# Light.net
KiCad netlist of a schematic drawn in Altium Designer
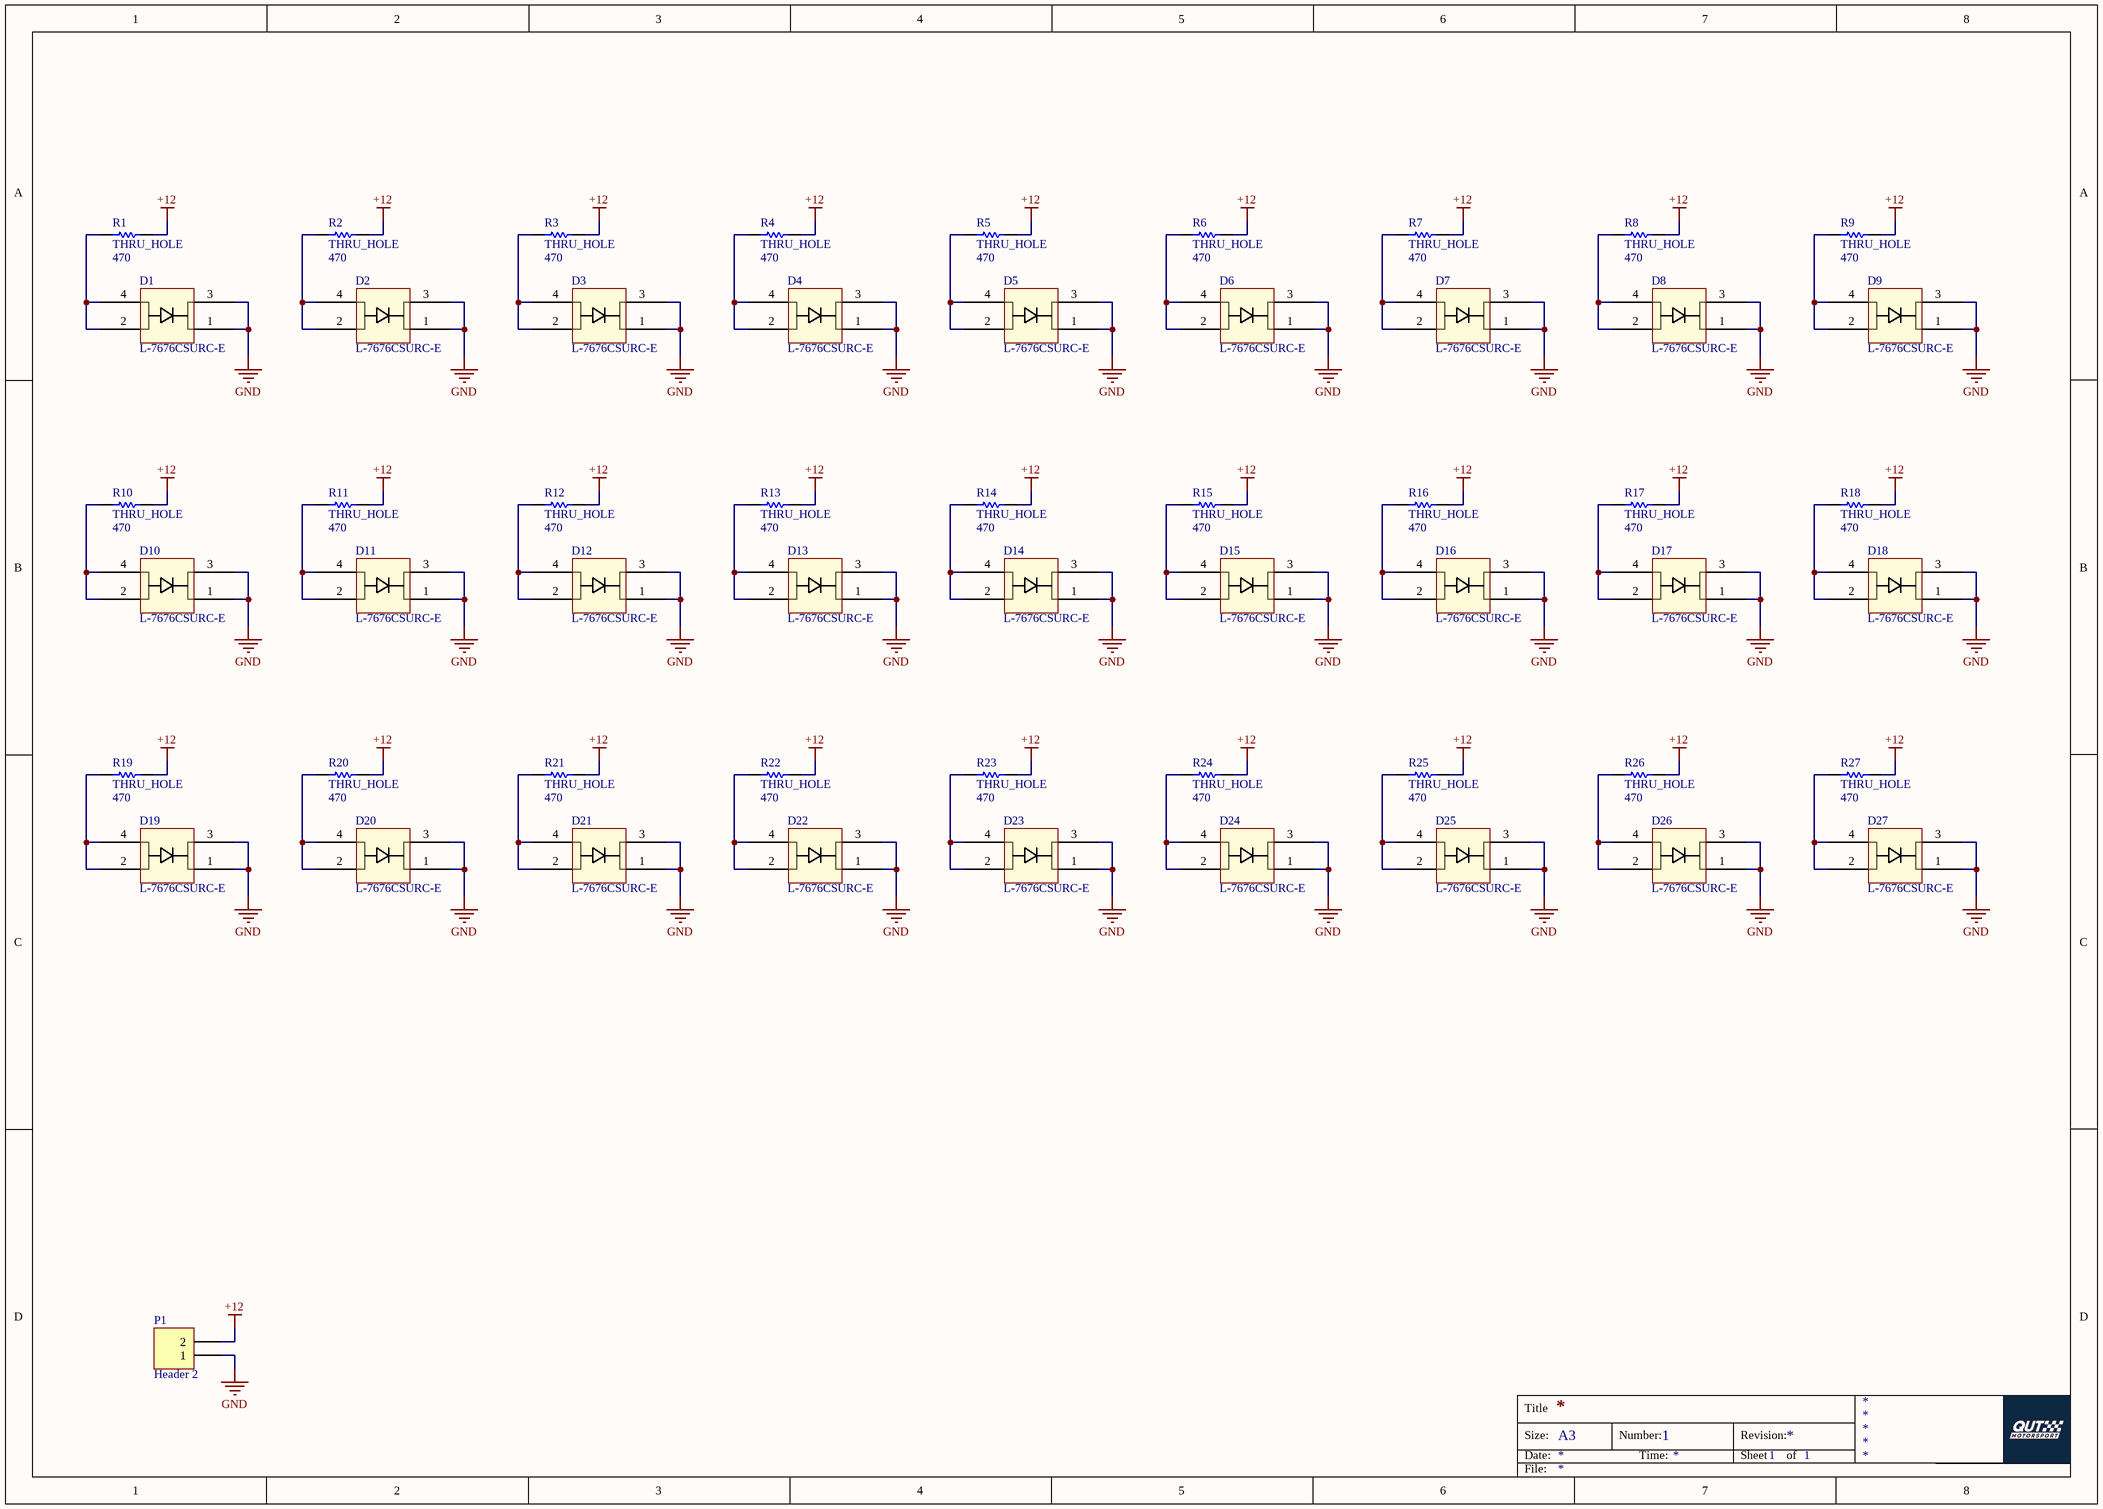
[diagram p0: Light.SchDoc]

(export (version "E")
  (design (tool "Eeschema 10.0.6"))
  (components
    (comp (ref "D1")
      (value "L-7676CSURC-E")
      (footprint "L-7676CSURC-E")
      (libsource (lib "BrightLED") (part "L-7676CSURC-E"))
    )
    (comp (ref "D2")
      (value "L-7676CSURC-E")
      (footprint "L-7676CSURC-E")
      (libsource (lib "BrightLED") (part "L-7676CSURC-E"))
    )
    (comp (ref "D3")
      (value "L-7676CSURC-E")
      (footprint "L-7676CSURC-E")
      (libsource (lib "BrightLED") (part "L-7676CSURC-E"))
    )
    (comp (ref "D4")
      (value "L-7676CSURC-E")
      (footprint "L-7676CSURC-E")
      (libsource (lib "BrightLED") (part "L-7676CSURC-E"))
    )
    (comp (ref "D5")
      (value "L-7676CSURC-E")
      (footprint "L-7676CSURC-E")
      (libsource (lib "BrightLED") (part "L-7676CSURC-E"))
    )
    (comp (ref "D6")
      (value "L-7676CSURC-E")
      (footprint "L-7676CSURC-E")
      (libsource (lib "BrightLED") (part "L-7676CSURC-E"))
    )
    (comp (ref "D7")
      (value "L-7676CSURC-E")
      (footprint "L-7676CSURC-E")
      (libsource (lib "BrightLED") (part "L-7676CSURC-E"))
    )
    (comp (ref "D8")
      (value "L-7676CSURC-E")
      (footprint "L-7676CSURC-E")
      (libsource (lib "BrightLED") (part "L-7676CSURC-E"))
    )
    (comp (ref "D9")
      (value "L-7676CSURC-E")
      (footprint "L-7676CSURC-E")
      (libsource (lib "BrightLED") (part "L-7676CSURC-E"))
    )
    (comp (ref "D10")
      (value "L-7676CSURC-E")
      (footprint "L-7676CSURC-E")
      (libsource (lib "BrightLED") (part "L-7676CSURC-E"))
    )
    (comp (ref "D11")
      (value "L-7676CSURC-E")
      (footprint "L-7676CSURC-E")
      (libsource (lib "BrightLED") (part "L-7676CSURC-E"))
    )
    (comp (ref "D12")
      (value "L-7676CSURC-E")
      (footprint "L-7676CSURC-E")
      (libsource (lib "BrightLED") (part "L-7676CSURC-E"))
    )
    (comp (ref "D13")
      (value "L-7676CSURC-E")
      (footprint "L-7676CSURC-E")
      (libsource (lib "BrightLED") (part "L-7676CSURC-E"))
    )
    (comp (ref "D14")
      (value "L-7676CSURC-E")
      (footprint "L-7676CSURC-E")
      (libsource (lib "BrightLED") (part "L-7676CSURC-E"))
    )
    (comp (ref "D15")
      (value "L-7676CSURC-E")
      (footprint "L-7676CSURC-E")
      (libsource (lib "BrightLED") (part "L-7676CSURC-E"))
    )
    (comp (ref "D16")
      (value "L-7676CSURC-E")
      (footprint "L-7676CSURC-E")
      (libsource (lib "BrightLED") (part "L-7676CSURC-E"))
    )
    (comp (ref "D17")
      (value "L-7676CSURC-E")
      (footprint "L-7676CSURC-E")
      (libsource (lib "BrightLED") (part "L-7676CSURC-E"))
    )
    (comp (ref "D18")
      (value "L-7676CSURC-E")
      (footprint "L-7676CSURC-E")
      (libsource (lib "BrightLED") (part "L-7676CSURC-E"))
    )
    (comp (ref "D19")
      (value "L-7676CSURC-E")
      (footprint "L-7676CSURC-E")
      (libsource (lib "BrightLED") (part "L-7676CSURC-E"))
    )
    (comp (ref "D20")
      (value "L-7676CSURC-E")
      (footprint "L-7676CSURC-E")
      (libsource (lib "BrightLED") (part "L-7676CSURC-E"))
    )
    (comp (ref "D21")
      (value "L-7676CSURC-E")
      (footprint "L-7676CSURC-E")
      (libsource (lib "BrightLED") (part "L-7676CSURC-E"))
    )
    (comp (ref "D22")
      (value "L-7676CSURC-E")
      (footprint "L-7676CSURC-E")
      (libsource (lib "BrightLED") (part "L-7676CSURC-E"))
    )
    (comp (ref "D23")
      (value "L-7676CSURC-E")
      (footprint "L-7676CSURC-E")
      (libsource (lib "BrightLED") (part "L-7676CSURC-E"))
    )
    (comp (ref "D24")
      (value "L-7676CSURC-E")
      (footprint "L-7676CSURC-E")
      (libsource (lib "BrightLED") (part "L-7676CSURC-E"))
    )
    (comp (ref "D25")
      (value "L-7676CSURC-E")
      (footprint "L-7676CSURC-E")
      (libsource (lib "BrightLED") (part "L-7676CSURC-E"))
    )
    (comp (ref "D26")
      (value "L-7676CSURC-E")
      (footprint "L-7676CSURC-E")
      (libsource (lib "BrightLED") (part "L-7676CSURC-E"))
    )
    (comp (ref "D27")
      (value "L-7676CSURC-E")
      (footprint "L-7676CSURC-E")
      (libsource (lib "BrightLED") (part "L-7676CSURC-E"))
    )
    (comp (ref "P1")
      (value "Header 2")
      (footprint "HDR1X2")
      (description "Header, 2-Pin")
      (fields (field (name "PUBLISHER") "Altium Limited"))
      (libsource (lib "Miscellaneous Connectors") (part "Header 2"))
    )
    (comp (ref "R1")
      (value "THRU_HOLE")
      (footprint "AXIAL-0.3")
      (description "Resistor")
      (fields (field (name "ALTIUM_VALUE") "470") (field (name "PUBLISHER") "Altium Limited"))
      (libsource (lib "Miscellaneous Devices") (part "Res1"))
    )
    (comp (ref "R2")
      (value "THRU_HOLE")
      (footprint "AXIAL-0.3")
      (description "Resistor")
      (fields (field (name "ALTIUM_VALUE") "470") (field (name "PUBLISHER") "Altium Limited"))
      (libsource (lib "Miscellaneous Devices") (part "Res1"))
    )
    (comp (ref "R3")
      (value "THRU_HOLE")
      (footprint "AXIAL-0.3")
      (description "Resistor")
      (fields (field (name "ALTIUM_VALUE") "470") (field (name "PUBLISHER") "Altium Limited"))
      (libsource (lib "Miscellaneous Devices") (part "Res1"))
    )
    (comp (ref "R4")
      (value "THRU_HOLE")
      (footprint "AXIAL-0.3")
      (description "Resistor")
      (fields (field (name "ALTIUM_VALUE") "470") (field (name "PUBLISHER") "Altium Limited"))
      (libsource (lib "Miscellaneous Devices") (part "Res1"))
    )
    (comp (ref "R5")
      (value "THRU_HOLE")
      (footprint "AXIAL-0.3")
      (description "Resistor")
      (fields (field (name "ALTIUM_VALUE") "470") (field (name "PUBLISHER") "Altium Limited"))
      (libsource (lib "Miscellaneous Devices") (part "Res1"))
    )
    (comp (ref "R6")
      (value "THRU_HOLE")
      (footprint "AXIAL-0.3")
      (description "Resistor")
      (fields (field (name "ALTIUM_VALUE") "470") (field (name "PUBLISHER") "Altium Limited"))
      (libsource (lib "Miscellaneous Devices") (part "Res1"))
    )
    (comp (ref "R7")
      (value "THRU_HOLE")
      (footprint "AXIAL-0.3")
      (description "Resistor")
      (fields (field (name "ALTIUM_VALUE") "470") (field (name "PUBLISHER") "Altium Limited"))
      (libsource (lib "Miscellaneous Devices") (part "Res1"))
    )
    (comp (ref "R8")
      (value "THRU_HOLE")
      (footprint "AXIAL-0.3")
      (description "Resistor")
      (fields (field (name "ALTIUM_VALUE") "470") (field (name "PUBLISHER") "Altium Limited"))
      (libsource (lib "Miscellaneous Devices") (part "Res1"))
    )
    (comp (ref "R9")
      (value "THRU_HOLE")
      (footprint "AXIAL-0.3")
      (description "Resistor")
      (fields (field (name "ALTIUM_VALUE") "470") (field (name "PUBLISHER") "Altium Limited"))
      (libsource (lib "Miscellaneous Devices") (part "Res1"))
    )
    (comp (ref "R10")
      (value "THRU_HOLE")
      (footprint "AXIAL-0.3")
      (description "Resistor")
      (fields (field (name "ALTIUM_VALUE") "470") (field (name "PUBLISHER") "Altium Limited"))
      (libsource (lib "Miscellaneous Devices") (part "Res1"))
    )
    (comp (ref "R11")
      (value "THRU_HOLE")
      (footprint "AXIAL-0.3")
      (description "Resistor")
      (fields (field (name "ALTIUM_VALUE") "470") (field (name "PUBLISHER") "Altium Limited"))
      (libsource (lib "Miscellaneous Devices") (part "Res1"))
    )
    (comp (ref "R12")
      (value "THRU_HOLE")
      (footprint "AXIAL-0.3")
      (description "Resistor")
      (fields (field (name "ALTIUM_VALUE") "470") (field (name "PUBLISHER") "Altium Limited"))
      (libsource (lib "Miscellaneous Devices") (part "Res1"))
    )
    (comp (ref "R13")
      (value "THRU_HOLE")
      (footprint "AXIAL-0.3")
      (description "Resistor")
      (fields (field (name "ALTIUM_VALUE") "470") (field (name "PUBLISHER") "Altium Limited"))
      (libsource (lib "Miscellaneous Devices") (part "Res1"))
    )
    (comp (ref "R14")
      (value "THRU_HOLE")
      (footprint "AXIAL-0.3")
      (description "Resistor")
      (fields (field (name "ALTIUM_VALUE") "470") (field (name "PUBLISHER") "Altium Limited"))
      (libsource (lib "Miscellaneous Devices") (part "Res1"))
    )
    (comp (ref "R15")
      (value "THRU_HOLE")
      (footprint "AXIAL-0.3")
      (description "Resistor")
      (fields (field (name "ALTIUM_VALUE") "470") (field (name "PUBLISHER") "Altium Limited"))
      (libsource (lib "Miscellaneous Devices") (part "Res1"))
    )
    (comp (ref "R16")
      (value "THRU_HOLE")
      (footprint "AXIAL-0.3")
      (description "Resistor")
      (fields (field (name "ALTIUM_VALUE") "470") (field (name "PUBLISHER") "Altium Limited"))
      (libsource (lib "Miscellaneous Devices") (part "Res1"))
    )
    (comp (ref "R17")
      (value "THRU_HOLE")
      (footprint "AXIAL-0.3")
      (description "Resistor")
      (fields (field (name "ALTIUM_VALUE") "470") (field (name "PUBLISHER") "Altium Limited"))
      (libsource (lib "Miscellaneous Devices") (part "Res1"))
    )
    (comp (ref "R18")
      (value "THRU_HOLE")
      (footprint "AXIAL-0.3")
      (description "Resistor")
      (fields (field (name "ALTIUM_VALUE") "470") (field (name "PUBLISHER") "Altium Limited"))
      (libsource (lib "Miscellaneous Devices") (part "Res1"))
    )
    (comp (ref "R19")
      (value "THRU_HOLE")
      (footprint "AXIAL-0.3")
      (description "Resistor")
      (fields (field (name "ALTIUM_VALUE") "470") (field (name "PUBLISHER") "Altium Limited"))
      (libsource (lib "Miscellaneous Devices") (part "Res1"))
    )
    (comp (ref "R20")
      (value "THRU_HOLE")
      (footprint "AXIAL-0.3")
      (description "Resistor")
      (fields (field (name "ALTIUM_VALUE") "470") (field (name "PUBLISHER") "Altium Limited"))
      (libsource (lib "Miscellaneous Devices") (part "Res1"))
    )
    (comp (ref "R21")
      (value "THRU_HOLE")
      (footprint "AXIAL-0.3")
      (description "Resistor")
      (fields (field (name "ALTIUM_VALUE") "470") (field (name "PUBLISHER") "Altium Limited"))
      (libsource (lib "Miscellaneous Devices") (part "Res1"))
    )
    (comp (ref "R22")
      (value "THRU_HOLE")
      (footprint "AXIAL-0.3")
      (description "Resistor")
      (fields (field (name "ALTIUM_VALUE") "470") (field (name "PUBLISHER") "Altium Limited"))
      (libsource (lib "Miscellaneous Devices") (part "Res1"))
    )
    (comp (ref "R23")
      (value "THRU_HOLE")
      (footprint "AXIAL-0.3")
      (description "Resistor")
      (fields (field (name "ALTIUM_VALUE") "470") (field (name "PUBLISHER") "Altium Limited"))
      (libsource (lib "Miscellaneous Devices") (part "Res1"))
    )
    (comp (ref "R24")
      (value "THRU_HOLE")
      (footprint "AXIAL-0.3")
      (description "Resistor")
      (fields (field (name "ALTIUM_VALUE") "470") (field (name "PUBLISHER") "Altium Limited"))
      (libsource (lib "Miscellaneous Devices") (part "Res1"))
    )
    (comp (ref "R25")
      (value "THRU_HOLE")
      (footprint "AXIAL-0.3")
      (description "Resistor")
      (fields (field (name "ALTIUM_VALUE") "470") (field (name "PUBLISHER") "Altium Limited"))
      (libsource (lib "Miscellaneous Devices") (part "Res1"))
    )
    (comp (ref "R26")
      (value "THRU_HOLE")
      (footprint "AXIAL-0.3")
      (description "Resistor")
      (fields (field (name "ALTIUM_VALUE") "470") (field (name "PUBLISHER") "Altium Limited"))
      (libsource (lib "Miscellaneous Devices") (part "Res1"))
    )
    (comp (ref "R27")
      (value "THRU_HOLE")
      (footprint "AXIAL-0.3")
      (description "Resistor")
      (fields (field (name "ALTIUM_VALUE") "470") (field (name "PUBLISHER") "Altium Limited"))
      (libsource (lib "Miscellaneous Devices") (part "Res1"))
    )
  )
  (nets
    (net (code "1") (name "+12") (class "Default")
      (node (ref "P1") (pin "2") (pinfunction "2_2") (pintype "passive"))
      (node (ref "R1") (pin "2") (pinfunction "2_2") (pintype "passive"))
      (node (ref "R10") (pin "2") (pinfunction "2_2") (pintype "passive"))
      (node (ref "R11") (pin "2") (pinfunction "2_2") (pintype "passive"))
      (node (ref "R12") (pin "2") (pinfunction "2_2") (pintype "passive"))
      (node (ref "R13") (pin "2") (pinfunction "2_2") (pintype "passive"))
      (node (ref "R14") (pin "2") (pinfunction "2_2") (pintype "passive"))
      (node (ref "R15") (pin "2") (pinfunction "2_2") (pintype "passive"))
      (node (ref "R16") (pin "2") (pinfunction "2_2") (pintype "passive"))
      (node (ref "R17") (pin "2") (pinfunction "2_2") (pintype "passive"))
      (node (ref "R18") (pin "2") (pinfunction "2_2") (pintype "passive"))
      (node (ref "R19") (pin "2") (pinfunction "2_2") (pintype "passive"))
      (node (ref "R2") (pin "2") (pinfunction "2_2") (pintype "passive"))
      (node (ref "R20") (pin "2") (pinfunction "2_2") (pintype "passive"))
      (node (ref "R21") (pin "2") (pinfunction "2_2") (pintype "passive"))
      (node (ref "R22") (pin "2") (pinfunction "2_2") (pintype "passive"))
      (node (ref "R23") (pin "2") (pinfunction "2_2") (pintype "passive"))
      (node (ref "R24") (pin "2") (pinfunction "2_2") (pintype "passive"))
      (node (ref "R25") (pin "2") (pinfunction "2_2") (pintype "passive"))
      (node (ref "R26") (pin "2") (pinfunction "2_2") (pintype "passive"))
      (node (ref "R27") (pin "2") (pinfunction "2_2") (pintype "passive"))
      (node (ref "R3") (pin "2") (pinfunction "2_2") (pintype "passive"))
      (node (ref "R4") (pin "2") (pinfunction "2_2") (pintype "passive"))
      (node (ref "R5") (pin "2") (pinfunction "2_2") (pintype "passive"))
      (node (ref "R6") (pin "2") (pinfunction "2_2") (pintype "passive"))
      (node (ref "R7") (pin "2") (pinfunction "2_2") (pintype "passive"))
      (node (ref "R8") (pin "2") (pinfunction "2_2") (pintype "passive"))
      (node (ref "R9") (pin "2") (pinfunction "2_2") (pintype "passive"))
    )
    (net (code "2") (name "GND") (class "Default")
      (node (ref "D1") (pin "1") (pinfunction "0_1") (pintype "passive"))
      (node (ref "D1") (pin "3") (pinfunction "0_3") (pintype "passive"))
      (node (ref "D10") (pin "1") (pinfunction "0_1") (pintype "passive"))
      (node (ref "D10") (pin "3") (pinfunction "0_3") (pintype "passive"))
      (node (ref "D11") (pin "1") (pinfunction "0_1") (pintype "passive"))
      (node (ref "D11") (pin "3") (pinfunction "0_3") (pintype "passive"))
      (node (ref "D12") (pin "1") (pinfunction "0_1") (pintype "passive"))
      (node (ref "D12") (pin "3") (pinfunction "0_3") (pintype "passive"))
      (node (ref "D13") (pin "1") (pinfunction "0_1") (pintype "passive"))
      (node (ref "D13") (pin "3") (pinfunction "0_3") (pintype "passive"))
      (node (ref "D14") (pin "1") (pinfunction "0_1") (pintype "passive"))
      (node (ref "D14") (pin "3") (pinfunction "0_3") (pintype "passive"))
      (node (ref "D15") (pin "1") (pinfunction "0_1") (pintype "passive"))
      (node (ref "D15") (pin "3") (pinfunction "0_3") (pintype "passive"))
      (node (ref "D16") (pin "1") (pinfunction "0_1") (pintype "passive"))
      (node (ref "D16") (pin "3") (pinfunction "0_3") (pintype "passive"))
      (node (ref "D17") (pin "1") (pinfunction "0_1") (pintype "passive"))
      (node (ref "D17") (pin "3") (pinfunction "0_3") (pintype "passive"))
      (node (ref "D18") (pin "1") (pinfunction "0_1") (pintype "passive"))
      (node (ref "D18") (pin "3") (pinfunction "0_3") (pintype "passive"))
      (node (ref "D19") (pin "1") (pinfunction "0_1") (pintype "passive"))
      (node (ref "D19") (pin "3") (pinfunction "0_3") (pintype "passive"))
      (node (ref "D2") (pin "1") (pinfunction "0_1") (pintype "passive"))
      (node (ref "D2") (pin "3") (pinfunction "0_3") (pintype "passive"))
      (node (ref "D20") (pin "1") (pinfunction "0_1") (pintype "passive"))
      (node (ref "D20") (pin "3") (pinfunction "0_3") (pintype "passive"))
      (node (ref "D21") (pin "1") (pinfunction "0_1") (pintype "passive"))
      (node (ref "D21") (pin "3") (pinfunction "0_3") (pintype "passive"))
      (node (ref "D22") (pin "1") (pinfunction "0_1") (pintype "passive"))
      (node (ref "D22") (pin "3") (pinfunction "0_3") (pintype "passive"))
      (node (ref "D23") (pin "1") (pinfunction "0_1") (pintype "passive"))
      (node (ref "D23") (pin "3") (pinfunction "0_3") (pintype "passive"))
      (node (ref "D24") (pin "1") (pinfunction "0_1") (pintype "passive"))
      (node (ref "D24") (pin "3") (pinfunction "0_3") (pintype "passive"))
      (node (ref "D25") (pin "1") (pinfunction "0_1") (pintype "passive"))
      (node (ref "D25") (pin "3") (pinfunction "0_3") (pintype "passive"))
      (node (ref "D26") (pin "1") (pinfunction "0_1") (pintype "passive"))
      (node (ref "D26") (pin "3") (pinfunction "0_3") (pintype "passive"))
      (node (ref "D27") (pin "1") (pinfunction "0_1") (pintype "passive"))
      (node (ref "D27") (pin "3") (pinfunction "0_3") (pintype "passive"))
      (node (ref "D3") (pin "1") (pinfunction "0_1") (pintype "passive"))
      (node (ref "D3") (pin "3") (pinfunction "0_3") (pintype "passive"))
      (node (ref "D4") (pin "1") (pinfunction "0_1") (pintype "passive"))
      (node (ref "D4") (pin "3") (pinfunction "0_3") (pintype "passive"))
      (node (ref "D5") (pin "1") (pinfunction "0_1") (pintype "passive"))
      (node (ref "D5") (pin "3") (pinfunction "0_3") (pintype "passive"))
      (node (ref "D6") (pin "1") (pinfunction "0_1") (pintype "passive"))
      (node (ref "D6") (pin "3") (pinfunction "0_3") (pintype "passive"))
      (node (ref "D7") (pin "1") (pinfunction "0_1") (pintype "passive"))
      (node (ref "D7") (pin "3") (pinfunction "0_3") (pintype "passive"))
      (node (ref "D8") (pin "1") (pinfunction "0_1") (pintype "passive"))
      (node (ref "D8") (pin "3") (pinfunction "0_3") (pintype "passive"))
      (node (ref "D9") (pin "1") (pinfunction "0_1") (pintype "passive"))
      (node (ref "D9") (pin "3") (pinfunction "0_3") (pintype "passive"))
      (node (ref "P1") (pin "1") (pinfunction "1_1") (pintype "passive"))
    )
    (net (code "3") (name "Net-(D1-0-Pad2)") (class "Default")
      (node (ref "D1") (pin "2") (pinfunction "0_2") (pintype "passive"))
      (node (ref "D1") (pin "4") (pinfunction "0_4") (pintype "passive"))
      (node (ref "R1") (pin "1") (pinfunction "1_1") (pintype "passive"))
    )
    (net (code "4") (name "Net-(D2-0-Pad2)") (class "Default")
      (node (ref "D2") (pin "2") (pinfunction "0_2") (pintype "passive"))
      (node (ref "D2") (pin "4") (pinfunction "0_4") (pintype "passive"))
      (node (ref "R2") (pin "1") (pinfunction "1_1") (pintype "passive"))
    )
    (net (code "5") (name "Net-(D3-0-Pad2)") (class "Default")
      (node (ref "D3") (pin "2") (pinfunction "0_2") (pintype "passive"))
      (node (ref "D3") (pin "4") (pinfunction "0_4") (pintype "passive"))
      (node (ref "R3") (pin "1") (pinfunction "1_1") (pintype "passive"))
    )
    (net (code "6") (name "Net-(D4-0-Pad2)") (class "Default")
      (node (ref "D4") (pin "2") (pinfunction "0_2") (pintype "passive"))
      (node (ref "D4") (pin "4") (pinfunction "0_4") (pintype "passive"))
      (node (ref "R4") (pin "1") (pinfunction "1_1") (pintype "passive"))
    )
    (net (code "7") (name "Net-(D5-0-Pad2)") (class "Default")
      (node (ref "D5") (pin "2") (pinfunction "0_2") (pintype "passive"))
      (node (ref "D5") (pin "4") (pinfunction "0_4") (pintype "passive"))
      (node (ref "R5") (pin "1") (pinfunction "1_1") (pintype "passive"))
    )
    (net (code "8") (name "Net-(D6-0-Pad2)") (class "Default")
      (node (ref "D6") (pin "2") (pinfunction "0_2") (pintype "passive"))
      (node (ref "D6") (pin "4") (pinfunction "0_4") (pintype "passive"))
      (node (ref "R6") (pin "1") (pinfunction "1_1") (pintype "passive"))
    )
    (net (code "9") (name "Net-(D7-0-Pad2)") (class "Default")
      (node (ref "D7") (pin "2") (pinfunction "0_2") (pintype "passive"))
      (node (ref "D7") (pin "4") (pinfunction "0_4") (pintype "passive"))
      (node (ref "R7") (pin "1") (pinfunction "1_1") (pintype "passive"))
    )
    (net (code "10") (name "Net-(D8-0-Pad2)") (class "Default")
      (node (ref "D8") (pin "2") (pinfunction "0_2") (pintype "passive"))
      (node (ref "D8") (pin "4") (pinfunction "0_4") (pintype "passive"))
      (node (ref "R8") (pin "1") (pinfunction "1_1") (pintype "passive"))
    )
    (net (code "11") (name "Net-(D9-0-Pad2)") (class "Default")
      (node (ref "D9") (pin "2") (pinfunction "0_2") (pintype "passive"))
      (node (ref "D9") (pin "4") (pinfunction "0_4") (pintype "passive"))
      (node (ref "R9") (pin "1") (pinfunction "1_1") (pintype "passive"))
    )
    (net (code "12") (name "Net-(D10-0-Pad2)") (class "Default")
      (node (ref "D10") (pin "2") (pinfunction "0_2") (pintype "passive"))
      (node (ref "D10") (pin "4") (pinfunction "0_4") (pintype "passive"))
      (node (ref "R10") (pin "1") (pinfunction "1_1") (pintype "passive"))
    )
    (net (code "13") (name "Net-(D11-0-Pad2)") (class "Default")
      (node (ref "D11") (pin "2") (pinfunction "0_2") (pintype "passive"))
      (node (ref "D11") (pin "4") (pinfunction "0_4") (pintype "passive"))
      (node (ref "R11") (pin "1") (pinfunction "1_1") (pintype "passive"))
    )
    (net (code "14") (name "Net-(D12-0-Pad2)") (class "Default")
      (node (ref "D12") (pin "2") (pinfunction "0_2") (pintype "passive"))
      (node (ref "D12") (pin "4") (pinfunction "0_4") (pintype "passive"))
      (node (ref "R12") (pin "1") (pinfunction "1_1") (pintype "passive"))
    )
    (net (code "15") (name "Net-(D13-0-Pad2)") (class "Default")
      (node (ref "D13") (pin "2") (pinfunction "0_2") (pintype "passive"))
      (node (ref "D13") (pin "4") (pinfunction "0_4") (pintype "passive"))
      (node (ref "R13") (pin "1") (pinfunction "1_1") (pintype "passive"))
    )
    (net (code "16") (name "Net-(D14-0-Pad2)") (class "Default")
      (node (ref "D14") (pin "2") (pinfunction "0_2") (pintype "passive"))
      (node (ref "D14") (pin "4") (pinfunction "0_4") (pintype "passive"))
      (node (ref "R14") (pin "1") (pinfunction "1_1") (pintype "passive"))
    )
    (net (code "17") (name "Net-(D15-0-Pad2)") (class "Default")
      (node (ref "D15") (pin "2") (pinfunction "0_2") (pintype "passive"))
      (node (ref "D15") (pin "4") (pinfunction "0_4") (pintype "passive"))
      (node (ref "R15") (pin "1") (pinfunction "1_1") (pintype "passive"))
    )
    (net (code "18") (name "Net-(D16-0-Pad2)") (class "Default")
      (node (ref "D16") (pin "2") (pinfunction "0_2") (pintype "passive"))
      (node (ref "D16") (pin "4") (pinfunction "0_4") (pintype "passive"))
      (node (ref "R16") (pin "1") (pinfunction "1_1") (pintype "passive"))
    )
    (net (code "19") (name "Net-(D17-0-Pad2)") (class "Default")
      (node (ref "D17") (pin "2") (pinfunction "0_2") (pintype "passive"))
      (node (ref "D17") (pin "4") (pinfunction "0_4") (pintype "passive"))
      (node (ref "R17") (pin "1") (pinfunction "1_1") (pintype "passive"))
    )
    (net (code "20") (name "Net-(D18-0-Pad2)") (class "Default")
      (node (ref "D18") (pin "2") (pinfunction "0_2") (pintype "passive"))
      (node (ref "D18") (pin "4") (pinfunction "0_4") (pintype "passive"))
      (node (ref "R18") (pin "1") (pinfunction "1_1") (pintype "passive"))
    )
    (net (code "21") (name "Net-(D19-0-Pad2)") (class "Default")
      (node (ref "D19") (pin "2") (pinfunction "0_2") (pintype "passive"))
      (node (ref "D19") (pin "4") (pinfunction "0_4") (pintype "passive"))
      (node (ref "R19") (pin "1") (pinfunction "1_1") (pintype "passive"))
    )
    (net (code "22") (name "Net-(D20-0-Pad2)") (class "Default")
      (node (ref "D20") (pin "2") (pinfunction "0_2") (pintype "passive"))
      (node (ref "D20") (pin "4") (pinfunction "0_4") (pintype "passive"))
      (node (ref "R20") (pin "1") (pinfunction "1_1") (pintype "passive"))
    )
    (net (code "23") (name "Net-(D21-0-Pad2)") (class "Default")
      (node (ref "D21") (pin "2") (pinfunction "0_2") (pintype "passive"))
      (node (ref "D21") (pin "4") (pinfunction "0_4") (pintype "passive"))
      (node (ref "R21") (pin "1") (pinfunction "1_1") (pintype "passive"))
    )
    (net (code "24") (name "Net-(D22-0-Pad2)") (class "Default")
      (node (ref "D22") (pin "2") (pinfunction "0_2") (pintype "passive"))
      (node (ref "D22") (pin "4") (pinfunction "0_4") (pintype "passive"))
      (node (ref "R22") (pin "1") (pinfunction "1_1") (pintype "passive"))
    )
    (net (code "25") (name "Net-(D23-0-Pad2)") (class "Default")
      (node (ref "D23") (pin "2") (pinfunction "0_2") (pintype "passive"))
      (node (ref "D23") (pin "4") (pinfunction "0_4") (pintype "passive"))
      (node (ref "R23") (pin "1") (pinfunction "1_1") (pintype "passive"))
    )
    (net (code "26") (name "Net-(D24-0-Pad2)") (class "Default")
      (node (ref "D24") (pin "2") (pinfunction "0_2") (pintype "passive"))
      (node (ref "D24") (pin "4") (pinfunction "0_4") (pintype "passive"))
      (node (ref "R24") (pin "1") (pinfunction "1_1") (pintype "passive"))
    )
    (net (code "27") (name "Net-(D25-0-Pad2)") (class "Default")
      (node (ref "D25") (pin "2") (pinfunction "0_2") (pintype "passive"))
      (node (ref "D25") (pin "4") (pinfunction "0_4") (pintype "passive"))
      (node (ref "R25") (pin "1") (pinfunction "1_1") (pintype "passive"))
    )
    (net (code "28") (name "Net-(D26-0-Pad2)") (class "Default")
      (node (ref "D26") (pin "2") (pinfunction "0_2") (pintype "passive"))
      (node (ref "D26") (pin "4") (pinfunction "0_4") (pintype "passive"))
      (node (ref "R26") (pin "1") (pinfunction "1_1") (pintype "passive"))
    )
    (net (code "29") (name "Net-(D27-0-Pad2)") (class "Default")
      (node (ref "D27") (pin "2") (pinfunction "0_2") (pintype "passive"))
      (node (ref "D27") (pin "4") (pinfunction "0_4") (pintype "passive"))
      (node (ref "R27") (pin "1") (pinfunction "1_1") (pintype "passive"))
    )
  )
)
